# in3peltier.net
KiCad netlist of a schematic drawn in EAGLE
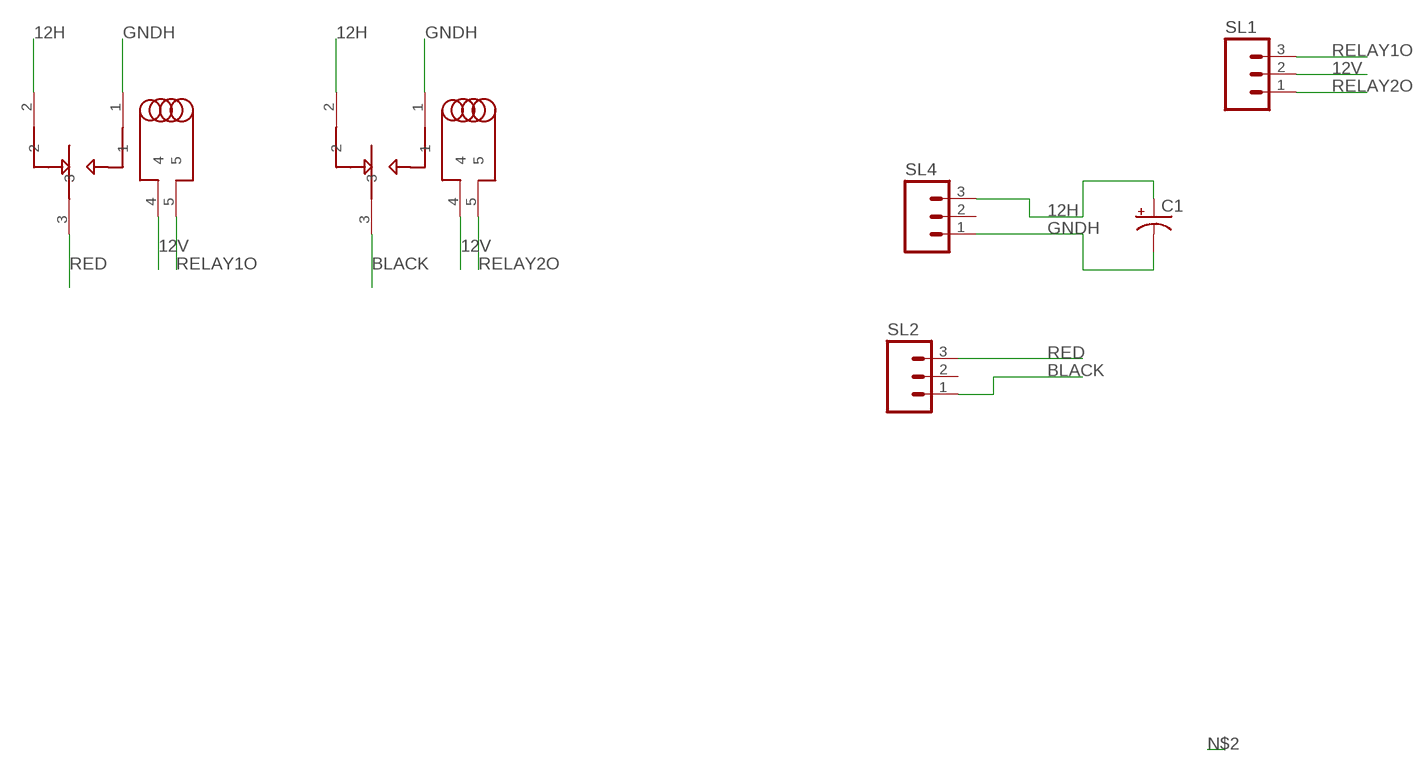
[diagram p0: schematic, sheet 1]

(export (version "E")
  (design (tool "Eeschema 10.0.6"))
  (components
    (comp (ref "C1")
      (value "CAP_POLPTH2")
      (footprint "eagle-import:CPOL-RADIAL-10UF-25V")
      (libsource (lib "eagle-import") (part "CAP_POLPTH2"))
    )
    (comp (ref "SL1")
      (value "MA03")
      (footprint "eagle-import:03P")
      (libsource (lib "eagle-import") (part "MA03"))
    )
    (comp (ref "SL2")
      (value "MA03")
      (footprint "eagle-import:03P")
      (libsource (lib "eagle-import") (part "MA03"))
    )
    (comp (ref "SL4")
      (value "MA03")
      (footprint "eagle-import:03P")
      (libsource (lib "eagle-import") (part "MA03"))
    )
    (comp (ref "U$1")
      (value "RELAY-V23092THROUGH_HOLE")
      (footprint "eagle-import:RELAY-V23092")
      (libsource (lib "eagle-import") (part "RELAY-V23092THROUGH_HOLE"))
    )
    (comp (ref "U$2")
      (value "RELAY-V23092THROUGH_HOLE")
      (footprint "eagle-import:RELAY-V23092")
      (libsource (lib "eagle-import") (part "RELAY-V23092THROUGH_HOLE"))
    )
  )
  (nets
    (net (code "1") (name "/12H") (class "Default")
      (node (ref "C1") (pin "1") (pinfunction "+_1") (pintype "passive"))
      (node (ref "SL4") (pin "3") (pinfunction "3_3") (pintype "passive"))
      (node (ref "U$1") (pin "2") (pinfunction "2_2") (pintype "bidirectional"))
      (node (ref "U$2") (pin "2") (pinfunction "2_2") (pintype "bidirectional"))
    )
    (net (code "2") (name "/12V") (class "Default")
      (node (ref "SL1") (pin "2") (pinfunction "2_2") (pintype "passive"))
      (node (ref "U$1") (pin "4") (pinfunction "4_4") (pintype "bidirectional"))
      (node (ref "U$2") (pin "4") (pinfunction "4_4") (pintype "bidirectional"))
    )
    (net (code "3") (name "/BLACK") (class "Default")
      (node (ref "SL2") (pin "1") (pinfunction "1_1") (pintype "passive"))
      (node (ref "U$2") (pin "3") (pinfunction "3_3") (pintype "bidirectional"))
    )
    (net (code "4") (name "/GNDH") (class "Default")
      (node (ref "C1") (pin "2") (pinfunction "-_2") (pintype "passive"))
      (node (ref "SL4") (pin "1") (pinfunction "1_1") (pintype "passive"))
      (node (ref "U$1") (pin "1") (pinfunction "1_1") (pintype "bidirectional"))
      (node (ref "U$2") (pin "1") (pinfunction "1_1") (pintype "bidirectional"))
    )
    (net (code "6") (name "/RED") (class "Default")
      (node (ref "SL2") (pin "3") (pinfunction "3_3") (pintype "passive"))
      (node (ref "U$1") (pin "3") (pinfunction "3_3") (pintype "bidirectional"))
    )
    (net (code "7") (name "/RELAY1O") (class "Default")
      (node (ref "SL1") (pin "3") (pinfunction "3_3") (pintype "passive"))
      (node (ref "U$1") (pin "5") (pinfunction "5_5") (pintype "bidirectional"))
    )
    (net (code "8") (name "/RELAY2O") (class "Default")
      (node (ref "SL1") (pin "1") (pinfunction "1_1") (pintype "passive"))
      (node (ref "U$2") (pin "5") (pinfunction "5_5") (pintype "bidirectional"))
    )
    (net (code "9") (name "unconnected-(SL2-Pad2)") (class "Default")
      (node (ref "SL2") (pin "2") (pinfunction "2_2") (pintype "passive"))
    )
    (net (code "10") (name "unconnected-(SL4-Pad2)") (class "Default")
      (node (ref "SL4") (pin "2") (pinfunction "2_2") (pintype "passive"))
    )
  )
)
